# connection_final.net
KiCad netlist of a schematic drawn in EAGLE
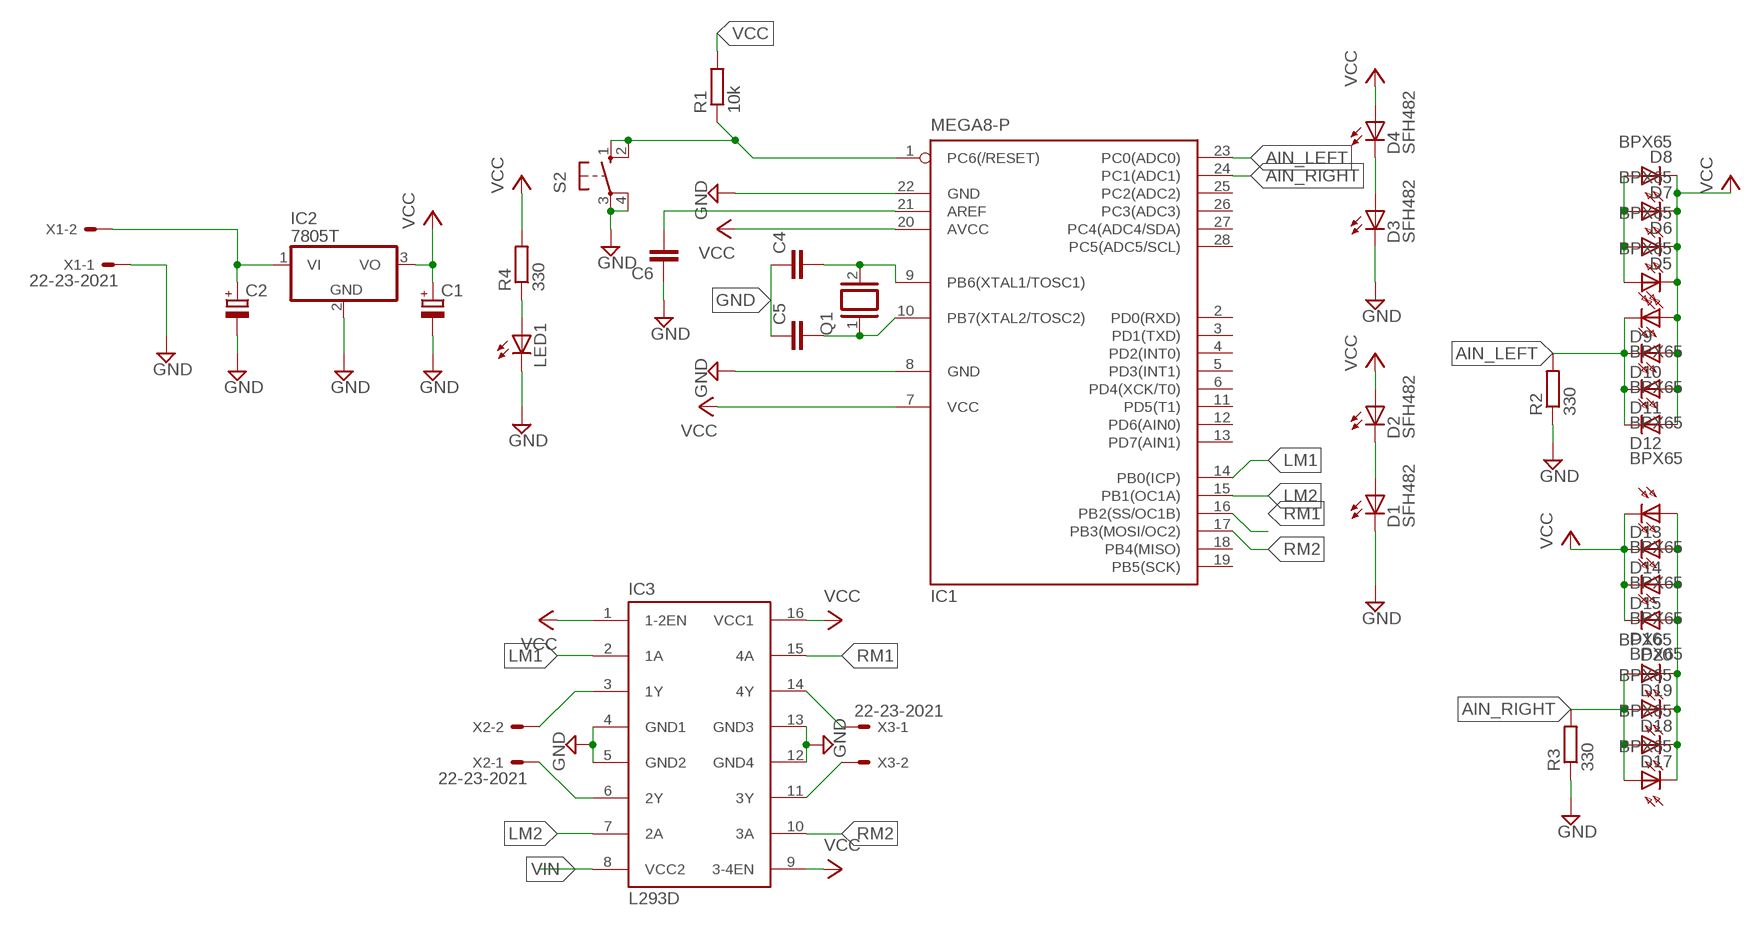
[diagram p0: schematic, sheet 1]

(export (version "E")
  (design (tool "Eeschema 10.0.6"))
  (components
    (comp (ref "C1")
      (value "CPOL-EUE3.5-8")
      (footprint "eagle-import:E3,5-8")
      (libsource (lib "eagle-import") (part "CPOL-EUE3.5-8"))
    )
    (comp (ref "C2")
      (value "CPOL-EUE3.5-8")
      (footprint "eagle-import:E3,5-8")
      (libsource (lib "eagle-import") (part "CPOL-EUE3.5-8"))
    )
    (comp (ref "C4")
      (value "C5/2.5")
      (footprint "eagle-import:C5B2.5")
      (libsource (lib "eagle-import") (part "C5/2.5"))
    )
    (comp (ref "C5")
      (value "C5/2.5")
      (footprint "eagle-import:C5B2.5")
      (libsource (lib "eagle-import") (part "C5/2.5"))
    )
    (comp (ref "C6")
      (value "C5/2.5")
      (footprint "eagle-import:C5B2.5")
      (libsource (lib "eagle-import") (part "C5/2.5"))
    )
    (comp (ref "D1")
      (value "SFH482")
      (footprint "eagle-import:SFH482")
      (libsource (lib "eagle-import") (part "SFH482"))
    )
    (comp (ref "D2")
      (value "SFH482")
      (footprint "eagle-import:SFH482")
      (libsource (lib "eagle-import") (part "SFH482"))
    )
    (comp (ref "D3")
      (value "SFH482")
      (footprint "eagle-import:SFH482")
      (libsource (lib "eagle-import") (part "SFH482"))
    )
    (comp (ref "D4")
      (value "SFH482")
      (footprint "eagle-import:SFH482")
      (libsource (lib "eagle-import") (part "SFH482"))
    )
    (comp (ref "D5")
      (value "BPX65")
      (footprint "eagle-import:BPX65")
      (fields (field (name "MPN") "BPX65."))
      (libsource (lib "eagle-import") (part "BPX65"))
    )
    (comp (ref "D6")
      (value "BPX65")
      (footprint "eagle-import:BPX65")
      (fields (field (name "MPN") "BPX65."))
      (libsource (lib "eagle-import") (part "BPX65"))
    )
    (comp (ref "D7")
      (value "BPX65")
      (footprint "eagle-import:BPX65")
      (fields (field (name "MPN") "BPX65."))
      (libsource (lib "eagle-import") (part "BPX65"))
    )
    (comp (ref "D8")
      (value "BPX65")
      (footprint "eagle-import:BPX65")
      (fields (field (name "MPN") "BPX65."))
      (libsource (lib "eagle-import") (part "BPX65"))
    )
    (comp (ref "D9")
      (value "BPX65")
      (footprint "eagle-import:BPX65")
      (fields (field (name "MPN") "BPX65."))
      (libsource (lib "eagle-import") (part "BPX65"))
    )
    (comp (ref "D10")
      (value "BPX65")
      (footprint "eagle-import:BPX65")
      (fields (field (name "MPN") "BPX65."))
      (libsource (lib "eagle-import") (part "BPX65"))
    )
    (comp (ref "D11")
      (value "BPX65")
      (footprint "eagle-import:BPX65")
      (fields (field (name "MPN") "BPX65."))
      (libsource (lib "eagle-import") (part "BPX65"))
    )
    (comp (ref "D12")
      (value "BPX65")
      (footprint "eagle-import:BPX65")
      (fields (field (name "MPN") "BPX65."))
      (libsource (lib "eagle-import") (part "BPX65"))
    )
    (comp (ref "D13")
      (value "BPX65")
      (footprint "eagle-import:BPX65")
      (fields (field (name "MPN") "BPX65."))
      (libsource (lib "eagle-import") (part "BPX65"))
    )
    (comp (ref "D14")
      (value "BPX65")
      (footprint "eagle-import:BPX65")
      (fields (field (name "MPN") "BPX65."))
      (libsource (lib "eagle-import") (part "BPX65"))
    )
    (comp (ref "D15")
      (value "BPX65")
      (footprint "eagle-import:BPX65")
      (fields (field (name "MPN") "BPX65."))
      (libsource (lib "eagle-import") (part "BPX65"))
    )
    (comp (ref "D16")
      (value "BPX65")
      (footprint "eagle-import:BPX65")
      (fields (field (name "MPN") "BPX65."))
      (libsource (lib "eagle-import") (part "BPX65"))
    )
    (comp (ref "D17")
      (value "BPX65")
      (footprint "eagle-import:BPX65")
      (fields (field (name "MPN") "BPX65."))
      (libsource (lib "eagle-import") (part "BPX65"))
    )
    (comp (ref "D18")
      (value "BPX65")
      (footprint "eagle-import:BPX65")
      (fields (field (name "MPN") "BPX65."))
      (libsource (lib "eagle-import") (part "BPX65"))
    )
    (comp (ref "D19")
      (value "BPX65")
      (footprint "eagle-import:BPX65")
      (fields (field (name "MPN") "BPX65."))
      (libsource (lib "eagle-import") (part "BPX65"))
    )
    (comp (ref "D20")
      (value "BPX65")
      (footprint "eagle-import:BPX65")
      (fields (field (name "MPN") "BPX65."))
      (libsource (lib "eagle-import") (part "BPX65"))
    )
    (comp (ref "IC1")
      (value "MEGA8-P")
      (footprint "eagle-import:DIL28-3")
      (libsource (lib "eagle-import") (part "MEGA8-P"))
    )
    (comp (ref "IC2")
      (value "7805T")
      (footprint "eagle-import:TO220H")
      (libsource (lib "eagle-import") (part "78T05"))
    )
    (comp (ref "IC3")
      (value "L293D")
      (footprint "eagle-import:DIL16")
      (libsource (lib "eagle-import") (part "L293D"))
    )
    (comp (ref "LED1")
      (value "LED5MM")
      (footprint "eagle-import:LED5MM")
      (libsource (lib "eagle-import") (part "LED5MM"))
    )
    (comp (ref "Q1")
      (value "XTAL/S")
      (footprint "eagle-import:QS")
      (libsource (lib "eagle-import") (part "XTAL/S"))
    )
    (comp (ref "R1")
      (value "10k")
      (footprint "eagle-import:0204_5")
      (libsource (lib "eagle-import") (part "R-EU_0204/5"))
    )
    (comp (ref "R2")
      (value "330")
      (footprint "eagle-import:0204_5")
      (libsource (lib "eagle-import") (part "R-EU_0204/5"))
    )
    (comp (ref "R3")
      (value "330")
      (footprint "eagle-import:0204_5")
      (libsource (lib "eagle-import") (part "R-EU_0204/5"))
    )
    (comp (ref "R4")
      (value "330")
      (footprint "eagle-import:0204_5")
      (libsource (lib "eagle-import") (part "R-EU_0204/5"))
    )
    (comp (ref "S2")
      (value "10-XX")
      (footprint "eagle-import:B3F-10XX")
      (fields (field (name "MPN") "B3F-1000"))
      (libsource (lib "eagle-import") (part "10-XX"))
    )
    (comp (ref "X1")
      (value "22-23-2021")
      (footprint "eagle-import:22-23-2021")
      (fields (field (name "MF") "MOLEX"))
      (libsource (lib "eagle-import") (part "22-23-2021"))
    )
    (comp (ref "X2")
      (value "22-23-2021")
      (footprint "eagle-import:22-23-2021")
      (fields (field (name "MF") "MOLEX"))
      (libsource (lib "eagle-import") (part "22-23-2021"))
    )
    (comp (ref "X3")
      (value "22-23-2021")
      (footprint "eagle-import:22-23-2021")
      (fields (field (name "MF") "MOLEX"))
      (libsource (lib "eagle-import") (part "22-23-2021"))
    )
  )
  (nets
    (net (code "1") (name "AIN_LEFT") (class "Default")
      (node (ref "D10") (pin "K") (pinfunction "C_K") (pintype "passive"))
      (node (ref "D11") (pin "K") (pinfunction "C_K") (pintype "passive"))
      (node (ref "D12") (pin "K") (pinfunction "C_K") (pintype "passive"))
      (node (ref "D9") (pin "K") (pinfunction "C_K") (pintype "passive"))
      (node (ref "IC1") (pin "23") (pinfunction "PC0(ADC0)_23") (pintype "bidirectional"))
      (node (ref "R2") (pin "2") (pinfunction "2_2") (pintype "passive"))
    )
    (net (code "2") (name "AIN_RIGHT") (class "Default")
      (node (ref "D17") (pin "A") (pinfunction "A_A") (pintype "passive"))
      (node (ref "D18") (pin "A") (pinfunction "A_A") (pintype "passive"))
      (node (ref "D19") (pin "A") (pinfunction "A_A") (pintype "passive"))
      (node (ref "D20") (pin "A") (pinfunction "A_A") (pintype "passive"))
      (node (ref "IC1") (pin "24") (pinfunction "PC1(ADC1)_24") (pintype "bidirectional"))
      (node (ref "R3") (pin "2") (pinfunction "2_2") (pintype "passive"))
    )
    (net (code "3") (name "GND") (class "Default")
      (node (ref "C1") (pin "-") (pinfunction "-_-") (pintype "passive"))
      (node (ref "C2") (pin "-") (pinfunction "-_-") (pintype "passive"))
      (node (ref "C4") (pin "1") (pinfunction "1_1") (pintype "passive"))
      (node (ref "C5") (pin "1") (pinfunction "1_1") (pintype "passive"))
      (node (ref "C6") (pin "1") (pinfunction "1_1") (pintype "passive"))
      (node (ref "D1") (pin "K") (pinfunction "C_K") (pintype "passive"))
      (node (ref "D3") (pin "K") (pinfunction "C_K") (pintype "passive"))
      (node (ref "IC1") (pin "22") (pinfunction "GND_22") (pintype "power_in"))
      (node (ref "IC1") (pin "8") (pinfunction "GND_8") (pintype "power_in"))
      (node (ref "IC2") (pin "2") (pinfunction "GND_2") (pintype "passive"))
      (node (ref "IC3") (pin "12") (pinfunction "GND4_12") (pintype "power_in"))
      (node (ref "IC3") (pin "13") (pinfunction "GND3_13") (pintype "power_in"))
      (node (ref "IC3") (pin "4") (pinfunction "GND1_4") (pintype "power_in"))
      (node (ref "IC3") (pin "5") (pinfunction "GND2_5") (pintype "power_in"))
      (node (ref "LED1") (pin "K") (pinfunction "C_K") (pintype "passive"))
      (node (ref "R2") (pin "1") (pinfunction "1_1") (pintype "passive"))
      (node (ref "R3") (pin "1") (pinfunction "1_1") (pintype "passive"))
      (node (ref "S2") (pin "3") (pinfunction "P_3") (pintype "passive"))
      (node (ref "S2") (pin "4") (pinfunction "P1_4") (pintype "passive"))
      (node (ref "X1") (pin "1") (pinfunction "S_1") (pintype "passive"))
    )
    (net (code "4") (name "LM1") (class "Default")
      (node (ref "IC1") (pin "14") (pinfunction "PB0(ICP)_14") (pintype "bidirectional"))
      (node (ref "IC3") (pin "2") (pinfunction "1A_2") (pintype "input"))
    )
    (net (code "5") (name "LM2") (class "Default")
      (node (ref "IC1") (pin "15") (pinfunction "PB1(OC1A)_15") (pintype "bidirectional"))
      (node (ref "IC3") (pin "7") (pinfunction "2A_7") (pintype "input"))
    )
    (net (code "6") (name "Net-(D2-C)") (class "Default")
      (node (ref "D1") (pin "A") (pinfunction "A_A") (pintype "passive"))
      (node (ref "D2") (pin "K") (pinfunction "C_K") (pintype "passive"))
    )
    (net (code "7") (name "Net-(D4-C)") (class "Default")
      (node (ref "D3") (pin "A") (pinfunction "A_A") (pintype "passive"))
      (node (ref "D4") (pin "K") (pinfunction "C_K") (pintype "passive"))
    )
    (net (code "8") (name "Net-(D5-PadA)") (class "Default")
      (node (ref "D5") (pin "A") (pinfunction "A_A") (pintype "passive"))
      (node (ref "D6") (pin "A") (pinfunction "A_A") (pintype "passive"))
      (node (ref "D7") (pin "A") (pinfunction "A_A") (pintype "passive"))
      (node (ref "D8") (pin "A") (pinfunction "A_A") (pintype "passive"))
    )
    (net (code "9") (name "Net-(D17-C)") (class "Default")
      (node (ref "D13") (pin "A") (pinfunction "A_A") (pintype "passive"))
      (node (ref "D14") (pin "A") (pinfunction "A_A") (pintype "passive"))
      (node (ref "D15") (pin "A") (pinfunction "A_A") (pintype "passive"))
      (node (ref "D16") (pin "A") (pinfunction "A_A") (pintype "passive"))
      (node (ref "D17") (pin "K") (pinfunction "C_K") (pintype "passive"))
      (node (ref "D18") (pin "K") (pinfunction "C_K") (pintype "passive"))
      (node (ref "D19") (pin "K") (pinfunction "C_K") (pintype "passive"))
      (node (ref "D20") (pin "K") (pinfunction "C_K") (pintype "passive"))
    )
    (net (code "10") (name "Net-(IC1-AREF)") (class "Default")
      (node (ref "C6") (pin "2") (pinfunction "2_2") (pintype "passive"))
      (node (ref "IC1") (pin "21") (pinfunction "AREF_21") (pintype "passive"))
    )
    (net (code "11") (name "Net-(IC1-PB6(XTAL1{slash}TOSC1))") (class "Default")
      (node (ref "C4") (pin "2") (pinfunction "2_2") (pintype "passive"))
      (node (ref "IC1") (pin "9") (pinfunction "PB6(XTAL1/TOSC1)_9") (pintype "bidirectional"))
      (node (ref "Q1") (pin "2") (pinfunction "2_2") (pintype "passive"))
    )
    (net (code "12") (name "Net-(IC1-PB7(XTAL2{slash}TOSC2))") (class "Default")
      (node (ref "C5") (pin "2") (pinfunction "2_2") (pintype "passive"))
      (node (ref "IC1") (pin "10") (pinfunction "PB7(XTAL2/TOSC2)_10") (pintype "bidirectional"))
      (node (ref "Q1") (pin "1") (pinfunction "1_1") (pintype "passive"))
    )
    (net (code "13") (name "Net-(IC1-PC6({slash}RESET))") (class "Default")
      (node (ref "IC1") (pin "1") (pinfunction "PC6(/RESET)_1") (pintype "bidirectional"))
      (node (ref "R1") (pin "1") (pinfunction "1_1") (pintype "passive"))
      (node (ref "S2") (pin "1") (pinfunction "S_1") (pintype "passive"))
      (node (ref "S2") (pin "2") (pinfunction "S1_2") (pintype "passive"))
    )
    (net (code "14") (name "Net-(IC3-1Y)") (class "Default")
      (node (ref "IC3") (pin "3") (pinfunction "1Y_3") (pintype "output"))
      (node (ref "X2") (pin "2") (pinfunction "S_2") (pintype "passive"))
    )
    (net (code "15") (name "Net-(IC3-2Y)") (class "Default")
      (node (ref "IC3") (pin "6") (pinfunction "2Y_6") (pintype "output"))
      (node (ref "X2") (pin "1") (pinfunction "S_1") (pintype "passive"))
    )
    (net (code "16") (name "Net-(IC3-3Y)") (class "Default")
      (node (ref "IC3") (pin "11") (pinfunction "3Y_11") (pintype "output"))
      (node (ref "X3") (pin "2") (pinfunction "S_2") (pintype "passive"))
    )
    (net (code "17") (name "Net-(IC3-4Y)") (class "Default")
      (node (ref "IC3") (pin "14") (pinfunction "4Y_14") (pintype "output"))
      (node (ref "X3") (pin "1") (pinfunction "S_1") (pintype "passive"))
    )
    (net (code "18") (name "Net-(LED1-PadA)") (class "Default")
      (node (ref "LED1") (pin "A") (pinfunction "A_A") (pintype "passive"))
      (node (ref "R4") (pin "1") (pinfunction "1_1") (pintype "passive"))
    )
    (net (code "19") (name "RM1") (class "Default")
      (node (ref "IC1") (pin "16") (pinfunction "PB2(SS/OC1B)_16") (pintype "bidirectional"))
      (node (ref "IC3") (pin "15") (pinfunction "4A_15") (pintype "input"))
    )
    (net (code "20") (name "RM2") (class "Default")
      (node (ref "IC1") (pin "17") (pinfunction "PB3(MOSI/OC2)_17") (pintype "bidirectional"))
      (node (ref "IC3") (pin "10") (pinfunction "3A_10") (pintype "input"))
    )
    (net (code "21") (name "VCC") (class "Default")
      (node (ref "C1") (pin "+") (pinfunction "+_+") (pintype "passive"))
      (node (ref "D10") (pin "A") (pinfunction "A_A") (pintype "passive"))
      (node (ref "D11") (pin "A") (pinfunction "A_A") (pintype "passive"))
      (node (ref "D12") (pin "A") (pinfunction "A_A") (pintype "passive"))
      (node (ref "D13") (pin "K") (pinfunction "C_K") (pintype "passive"))
      (node (ref "D14") (pin "K") (pinfunction "C_K") (pintype "passive"))
      (node (ref "D15") (pin "K") (pinfunction "C_K") (pintype "passive"))
      (node (ref "D16") (pin "K") (pinfunction "C_K") (pintype "passive"))
      (node (ref "D2") (pin "A") (pinfunction "A_A") (pintype "passive"))
      (node (ref "D4") (pin "A") (pinfunction "A_A") (pintype "passive"))
      (node (ref "D5") (pin "K") (pinfunction "C_K") (pintype "passive"))
      (node (ref "D6") (pin "K") (pinfunction "C_K") (pintype "passive"))
      (node (ref "D7") (pin "K") (pinfunction "C_K") (pintype "passive"))
      (node (ref "D8") (pin "K") (pinfunction "C_K") (pintype "passive"))
      (node (ref "D9") (pin "A") (pinfunction "A_A") (pintype "passive"))
      (node (ref "IC1") (pin "20") (pinfunction "AVCC_20") (pintype "power_in"))
      (node (ref "IC1") (pin "7") (pinfunction "VCC_7") (pintype "power_in"))
      (node (ref "IC2") (pin "3") (pinfunction "VO_3") (pintype "passive"))
      (node (ref "IC3") (pin "1") (pinfunction "1-2EN_1") (pintype "input"))
      (node (ref "IC3") (pin "16") (pinfunction "VCC1_16") (pintype "power_in"))
      (node (ref "IC3") (pin "9") (pinfunction "3-4EN_9") (pintype "input"))
      (node (ref "R1") (pin "2") (pinfunction "2_2") (pintype "passive"))
      (node (ref "R4") (pin "2") (pinfunction "2_2") (pintype "passive"))
    )
    (net (code "22") (name "VIN") (class "Default")
      (node (ref "C2") (pin "+") (pinfunction "+_+") (pintype "passive"))
      (node (ref "IC2") (pin "1") (pinfunction "VI_1") (pintype "input"))
      (node (ref "IC3") (pin "8") (pinfunction "VCC2_8") (pintype "power_in"))
      (node (ref "X1") (pin "2") (pinfunction "S_2") (pintype "passive"))
    )
    (net (code "23") (name "unconnected-(IC1-PB4(MISO)-Pad18)") (class "Default")
      (node (ref "IC1") (pin "18") (pinfunction "PB4(MISO)_18") (pintype "bidirectional"))
    )
    (net (code "24") (name "unconnected-(IC1-PB5(SCK)-Pad19)") (class "Default")
      (node (ref "IC1") (pin "19") (pinfunction "PB5(SCK)_19") (pintype "bidirectional"))
    )
    (net (code "25") (name "unconnected-(IC1-PC2(ADC2)-Pad25)") (class "Default")
      (node (ref "IC1") (pin "25") (pinfunction "PC2(ADC2)_25") (pintype "bidirectional"))
    )
    (net (code "26") (name "unconnected-(IC1-PC3(ADC3)-Pad26)") (class "Default")
      (node (ref "IC1") (pin "26") (pinfunction "PC3(ADC3)_26") (pintype "bidirectional"))
    )
    (net (code "27") (name "unconnected-(IC1-PC4(ADC4{slash}SDA)-Pad27)") (class "Default")
      (node (ref "IC1") (pin "27") (pinfunction "PC4(ADC4/SDA)_27") (pintype "bidirectional"))
    )
    (net (code "28") (name "unconnected-(IC1-PC5(ADC5{slash}SCL)-Pad28)") (class "Default")
      (node (ref "IC1") (pin "28") (pinfunction "PC5(ADC5/SCL)_28") (pintype "bidirectional"))
    )
    (net (code "29") (name "unconnected-(IC1-PD0(RXD)-Pad2)") (class "Default")
      (node (ref "IC1") (pin "2") (pinfunction "PD0(RXD)_2") (pintype "bidirectional"))
    )
    (net (code "30") (name "unconnected-(IC1-PD1(TXD)-Pad3)") (class "Default")
      (node (ref "IC1") (pin "3") (pinfunction "PD1(TXD)_3") (pintype "bidirectional"))
    )
    (net (code "31") (name "unconnected-(IC1-PD2(INT0)-Pad4)") (class "Default")
      (node (ref "IC1") (pin "4") (pinfunction "PD2(INT0)_4") (pintype "bidirectional"))
    )
    (net (code "32") (name "unconnected-(IC1-PD3(INT1)-Pad5)") (class "Default")
      (node (ref "IC1") (pin "5") (pinfunction "PD3(INT1)_5") (pintype "bidirectional"))
    )
    (net (code "33") (name "unconnected-(IC1-PD4(XCK{slash}T0)-Pad6)") (class "Default")
      (node (ref "IC1") (pin "6") (pinfunction "PD4(XCK/T0)_6") (pintype "bidirectional"))
    )
    (net (code "34") (name "unconnected-(IC1-PD5(T1)-Pad11)") (class "Default")
      (node (ref "IC1") (pin "11") (pinfunction "PD5(T1)_11") (pintype "bidirectional"))
    )
    (net (code "35") (name "unconnected-(IC1-PD6(AIN0)-Pad12)") (class "Default")
      (node (ref "IC1") (pin "12") (pinfunction "PD6(AIN0)_12") (pintype "bidirectional"))
    )
    (net (code "36") (name "unconnected-(IC1-PD7(AIN1)-Pad13)") (class "Default")
      (node (ref "IC1") (pin "13") (pinfunction "PD7(AIN1)_13") (pintype "bidirectional"))
    )
  )
)
